# USB_proSupply.net
KiCad netlist of a schematic drawn in EAGLE
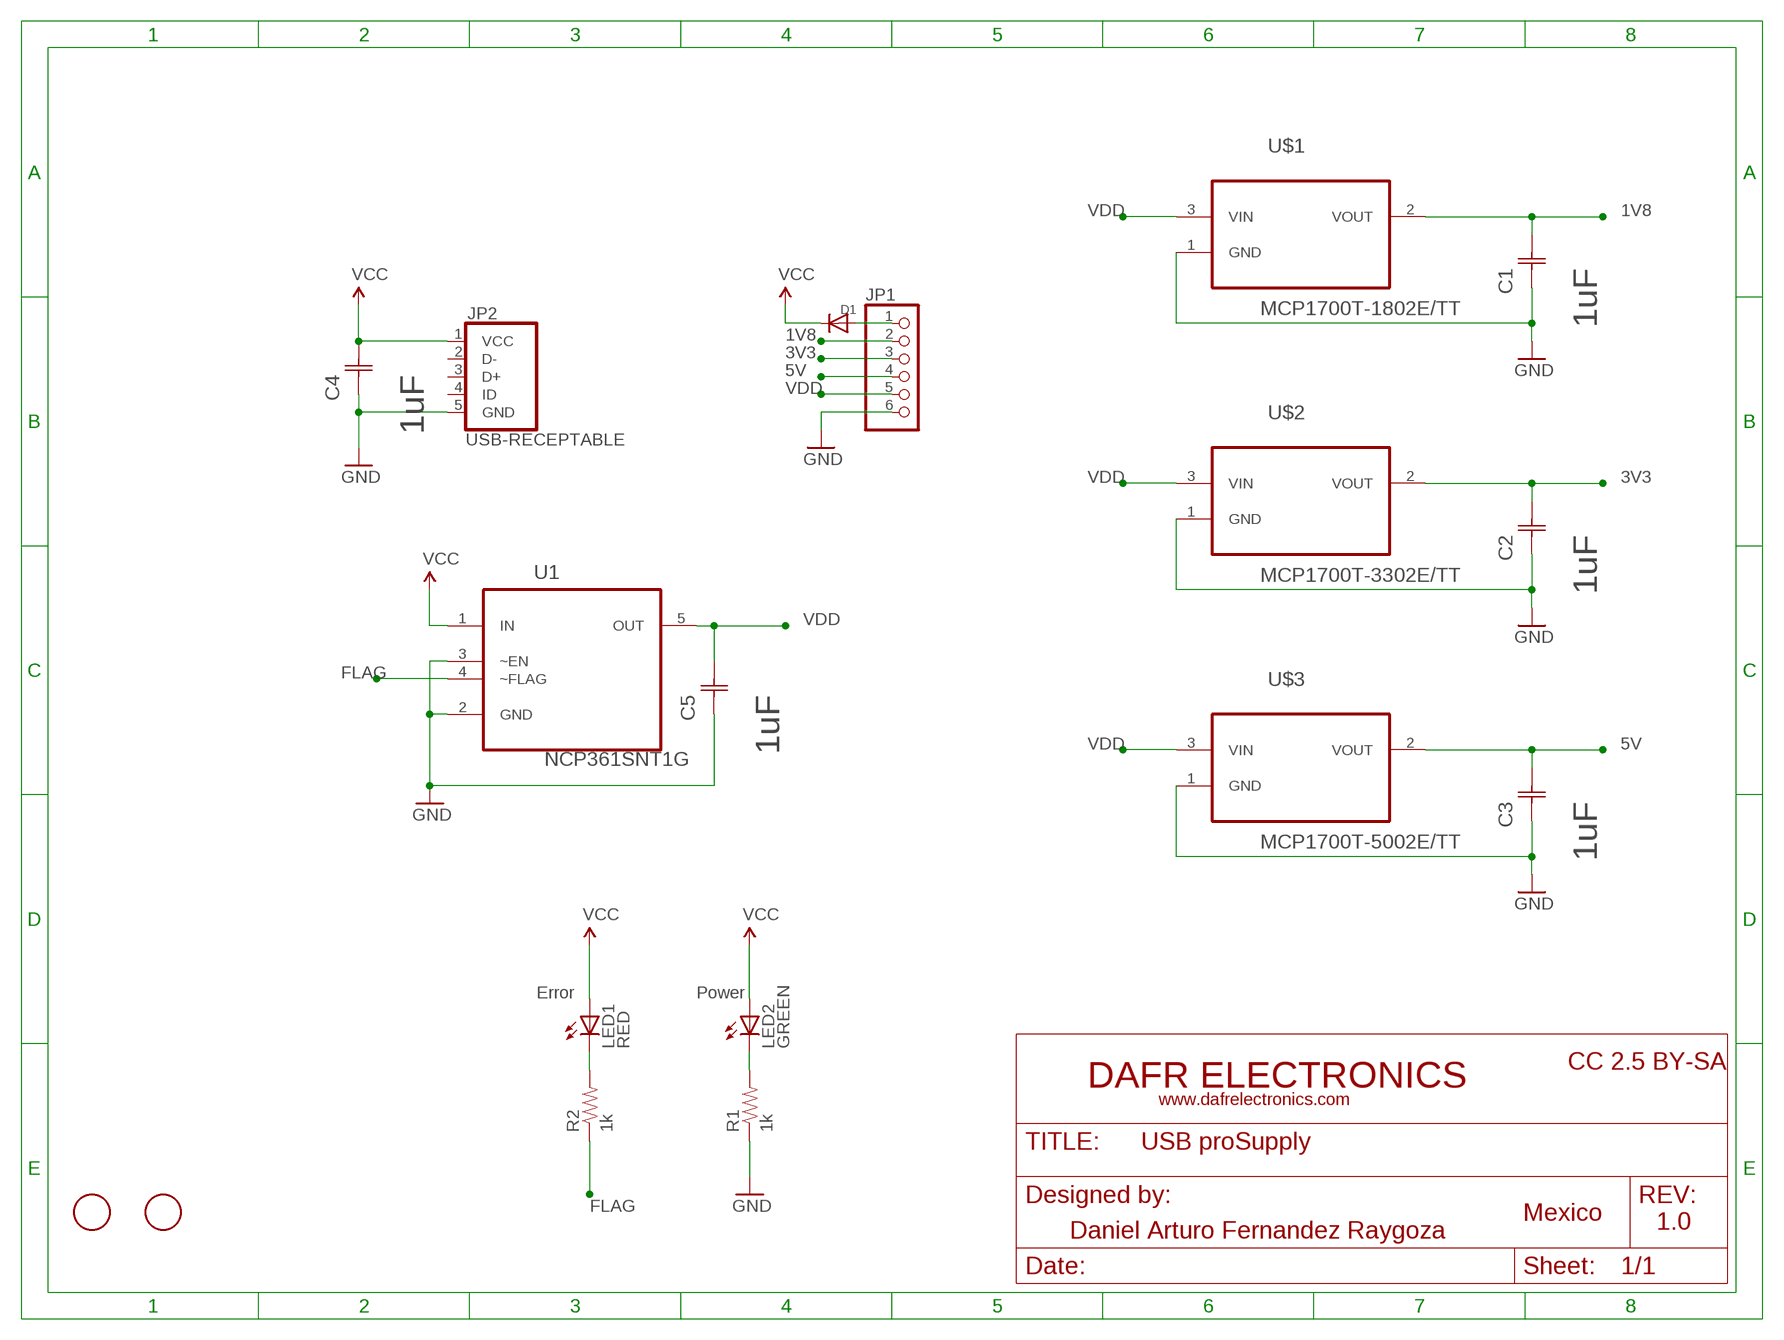
[diagram p0: schematic, sheet 1]

(export (version "E")
  (design (tool "Eeschema 10.0.6"))
  (components
    (comp (ref "C1")
      (value "1uF")
      (footprint "eagle-import:CAPC1608X94N")
      (fields (field (name "MPN") "06033D105KAT2A") (field (name "TOLERANCE") "±10%"))
      (libsource (lib "eagle-import") (part "06033D105KAT2A"))
    )
    (comp (ref "C2")
      (value "1uF")
      (footprint "eagle-import:CAPC1608X94N")
      (fields (field (name "MPN") "06033D105KAT2A") (field (name "TOLERANCE") "±10%"))
      (libsource (lib "eagle-import") (part "06033D105KAT2A"))
    )
    (comp (ref "C3")
      (value "1uF")
      (footprint "eagle-import:CAPC1608X94N")
      (fields (field (name "MPN") "06033D105KAT2A") (field (name "TOLERANCE") "±10%"))
      (libsource (lib "eagle-import") (part "06033D105KAT2A"))
    )
    (comp (ref "C4")
      (value "1uF")
      (footprint "eagle-import:CAPC1608X94N")
      (fields (field (name "MPN") "06033D105KAT2A") (field (name "TOLERANCE") "±10%"))
      (libsource (lib "eagle-import") (part "06033D105KAT2A"))
    )
    (comp (ref "C5")
      (value "1uF")
      (footprint "eagle-import:CAPC1608X94N")
      (fields (field (name "MPN") "06033D105KAT2A") (field (name "TOLERANCE") "±10%"))
      (libsource (lib "eagle-import") (part "06033D105KAT2A"))
    )
    (comp (ref "D1")
      (value "DIODESOD-123")
      (footprint "eagle-import:SOD-123")
      (libsource (lib "eagle-import") (part "DIODESOD-123"))
    )
    (comp (ref "JP1")
      (value "PINHD-1X6")
      (footprint "eagle-import:1X06")
      (libsource (lib "eagle-import") (part "PINHD-1X6"))
    )
    (comp (ref "JP2")
      (value "USB-RECEPTABLE")
      (footprint "eagle-import:FCI-10103594-0001LF")
      (libsource (lib "eagle-import") (part "USB-RECEPTABLE"))
    )
    (comp (ref "LED1")
      (value "RED")
      (footprint "eagle-import:CHIPLED_1206")
      (libsource (lib "eagle-import") (part "LEDCHIPLED_1206"))
    )
    (comp (ref "LED2")
      (value "GREEN")
      (footprint "eagle-import:CHIPLED_1206")
      (libsource (lib "eagle-import") (part "LEDCHIPLED_1206"))
    )
    (comp (ref "R1")
      (value "1k")
      (footprint "eagle-import:0805")
      (libsource (lib "eagle-import") (part "RESISTOR0805-RES"))
    )
    (comp (ref "R2")
      (value "1k")
      (footprint "eagle-import:0805")
      (libsource (lib "eagle-import") (part "RESISTOR0805-RES"))
    )
    (comp (ref "U$1")
      (value "MCP1700T-1802E/TT")
      (footprint "eagle-import:SOT95P237X112-3N")
      (libsource (lib "eagle-import") (part "MCP1700T-1802E/TT"))
    )
    (comp (ref "U$2")
      (value "MCP1700T-3302E/TT")
      (footprint "eagle-import:SOT95P237X112-3N")
      (libsource (lib "eagle-import") (part "MCP1700T-3302E/TT"))
    )
    (comp (ref "U$3")
      (value "MCP1700T-5002E/TT")
      (footprint "eagle-import:SOT95P237X112-3N")
      (libsource (lib "eagle-import") (part "MCP1700T-5002E/TT"))
    )
    (comp (ref "U$5")
      (value "FIDUCIAL")
      (footprint "eagle-import:FIDUCIAL_1MM")
      (libsource (lib "eagle-import") (part "FIDUCIAL"))
    )
    (comp (ref "U$6")
      (value "FIDUCIAL")
      (footprint "eagle-import:FIDUCIAL_1MM")
      (libsource (lib "eagle-import") (part "FIDUCIAL"))
    )
    (comp (ref "U1")
      (value "NCP361SNT1G")
      (footprint "eagle-import:SOP95P275X110-5N")
      (libsource (lib "eagle-import") (part "NCP361SNT1G"))
    )
  )
  (nets
    (net (code "1") (name "/1V8") (class "Default")
      (node (ref "C1") (pin "2") (pinfunction "C2_2") (pintype "passive"))
      (node (ref "JP1") (pin "2") (pinfunction "2_2") (pintype "passive"))
      (node (ref "U$1") (pin "2") (pinfunction "VOUT_2") (pintype "output"))
    )
    (net (code "2") (name "/3V3") (class "Default")
      (node (ref "C2") (pin "2") (pinfunction "C2_2") (pintype "passive"))
      (node (ref "JP1") (pin "3") (pinfunction "3_3") (pintype "passive"))
      (node (ref "U$2") (pin "2") (pinfunction "VOUT_2") (pintype "output"))
    )
    (net (code "3") (name "/5V") (class "Default")
      (node (ref "C3") (pin "2") (pinfunction "C2_2") (pintype "passive"))
      (node (ref "JP1") (pin "4") (pinfunction "4_4") (pintype "passive"))
      (node (ref "U$3") (pin "2") (pinfunction "VOUT_2") (pintype "output"))
    )
    (net (code "4") (name "/FLAG") (class "Default")
      (node (ref "R2") (pin "1") (pinfunction "1_1") (pintype "passive"))
      (node (ref "U1") (pin "4") (pinfunction "~{FLAG}_4") (pintype "input"))
    )
    (net (code "5") (name "/VDD") (class "Default")
      (node (ref "C5") (pin "2") (pinfunction "C2_2") (pintype "passive"))
      (node (ref "JP1") (pin "5") (pinfunction "5_5") (pintype "passive"))
      (node (ref "U$1") (pin "3") (pinfunction "VIN_3") (pintype "input"))
      (node (ref "U$2") (pin "3") (pinfunction "VIN_3") (pintype "input"))
      (node (ref "U$3") (pin "3") (pinfunction "VIN_3") (pintype "input"))
      (node (ref "U1") (pin "5") (pinfunction "OUT_5") (pintype "output"))
    )
    (net (code "6") (name "GND") (class "Default")
      (node (ref "C1") (pin "1") (pinfunction "C1_1") (pintype "passive"))
      (node (ref "C2") (pin "1") (pinfunction "C1_1") (pintype "passive"))
      (node (ref "C3") (pin "1") (pinfunction "C1_1") (pintype "passive"))
      (node (ref "C4") (pin "1") (pinfunction "C1_1") (pintype "passive"))
      (node (ref "C5") (pin "1") (pinfunction "C1_1") (pintype "passive"))
      (node (ref "JP1") (pin "6") (pinfunction "6_6") (pintype "passive"))
      (node (ref "JP2") (pin "5") (pinfunction "GND_5") (pintype "bidirectional"))
      (node (ref "R1") (pin "1") (pinfunction "1_1") (pintype "passive"))
      (node (ref "U$1") (pin "1") (pinfunction "GND_1") (pintype "passive"))
      (node (ref "U$2") (pin "1") (pinfunction "GND_1") (pintype "passive"))
      (node (ref "U$3") (pin "1") (pinfunction "GND_1") (pintype "passive"))
      (node (ref "U1") (pin "2") (pinfunction "GND_2") (pintype "passive"))
      (node (ref "U1") (pin "3") (pinfunction "~{EN}_3") (pintype "input"))
    )
    (net (code "7") (name "Net-(D1-PadA)") (class "Default")
      (node (ref "D1") (pin "A") (pinfunction "A_A") (pintype "passive"))
      (node (ref "JP1") (pin "1") (pinfunction "1_1") (pintype "passive"))
    )
    (net (code "8") (name "Net-(LED1-PadC)") (class "Default")
      (node (ref "LED1") (pin "C") (pinfunction "C_C") (pintype "passive"))
      (node (ref "R2") (pin "2") (pinfunction "2_2") (pintype "passive"))
    )
    (net (code "9") (name "Net-(LED2-PadC)") (class "Default")
      (node (ref "LED2") (pin "C") (pinfunction "C_C") (pintype "passive"))
      (node (ref "R1") (pin "2") (pinfunction "2_2") (pintype "passive"))
    )
    (net (code "10") (name "VCC") (class "Default")
      (node (ref "C4") (pin "2") (pinfunction "C2_2") (pintype "passive"))
      (node (ref "D1") (pin "C") (pinfunction "C_C") (pintype "passive"))
      (node (ref "JP2") (pin "1") (pinfunction "VCC_1") (pintype "bidirectional"))
      (node (ref "LED1") (pin "A") (pinfunction "A_A") (pintype "passive"))
      (node (ref "LED2") (pin "A") (pinfunction "A_A") (pintype "passive"))
      (node (ref "U1") (pin "1") (pinfunction "IN_1") (pintype "power_in"))
    )
    (net (code "11") (name "unconnected-(JP2-D+-Pad3)") (class "Default")
      (node (ref "JP2") (pin "3") (pinfunction "D+_3") (pintype "bidirectional"))
    )
    (net (code "12") (name "unconnected-(JP2-D--Pad2)") (class "Default")
      (node (ref "JP2") (pin "2") (pinfunction "D-_2") (pintype "bidirectional"))
    )
    (net (code "13") (name "unconnected-(JP2-ID-Pad4)") (class "Default")
      (node (ref "JP2") (pin "4") (pinfunction "ID_4") (pintype "bidirectional"))
    )
  )
)
